# M594B.net
KiCad netlist of a schematic drawn in EAGLE
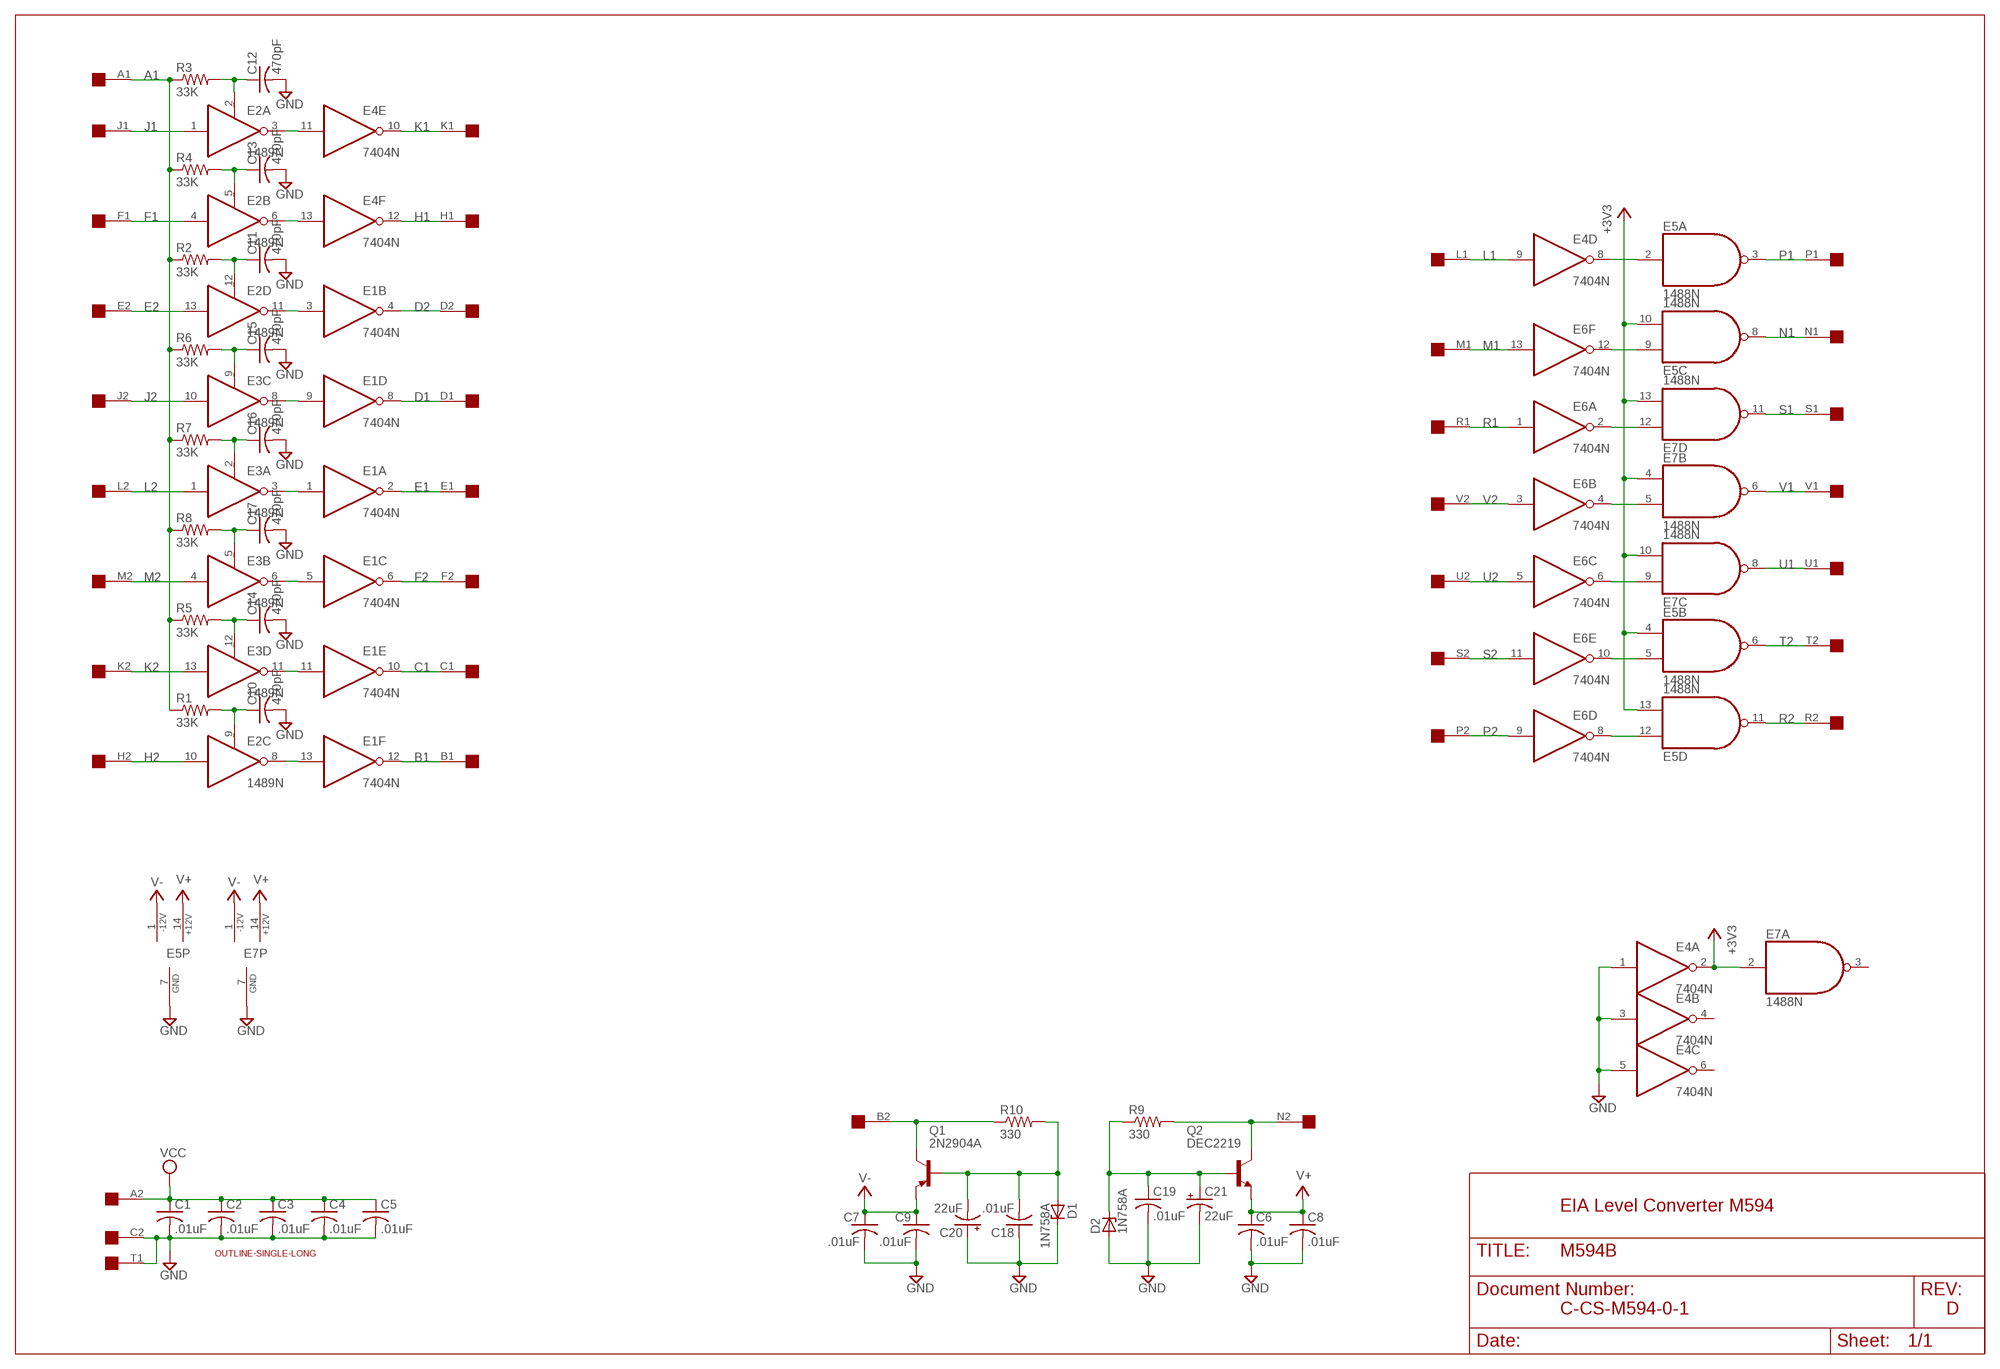
[diagram p0: schematic, sheet 1]

(export (version "E")
  (design (tool "Eeschema 10.0.6"))
  (components
    (comp (ref "C1")
      (value ".01uF")
      (footprint "eagle-import:C050-025X075")
      (libsource (lib "eagle-import") (part "C-US050-025X075"))
    )
    (comp (ref "C2")
      (value ".01uF")
      (footprint "eagle-import:C050-025X075")
      (libsource (lib "eagle-import") (part "C-US050-025X075"))
    )
    (comp (ref "C3")
      (value ".01uF")
      (footprint "eagle-import:C050-025X075")
      (libsource (lib "eagle-import") (part "C-US050-025X075"))
    )
    (comp (ref "C4")
      (value ".01uF")
      (footprint "eagle-import:C050-025X075")
      (libsource (lib "eagle-import") (part "C-US050-025X075"))
    )
    (comp (ref "C5")
      (value ".01uF")
      (footprint "eagle-import:C050-025X075")
      (libsource (lib "eagle-import") (part "C-US050-025X075"))
    )
    (comp (ref "C6")
      (value ".01uF")
      (footprint "eagle-import:C050-025X075")
      (libsource (lib "eagle-import") (part "C-US050-025X075"))
    )
    (comp (ref "C7")
      (value ".01uF")
      (footprint "eagle-import:C050-025X075")
      (libsource (lib "eagle-import") (part "C-US050-025X075"))
    )
    (comp (ref "C8")
      (value ".01uF")
      (footprint "eagle-import:C050-025X075")
      (libsource (lib "eagle-import") (part "C-US050-025X075"))
    )
    (comp (ref "C9")
      (value ".01uF")
      (footprint "eagle-import:C050-025X075")
      (libsource (lib "eagle-import") (part "C-US050-025X075"))
    )
    (comp (ref "C10")
      (value "470pF")
      (footprint "eagle-import:C075-032X103")
      (libsource (lib "eagle-import") (part "C-US075-032X103"))
    )
    (comp (ref "C11")
      (value "470pF")
      (footprint "eagle-import:C075-032X103")
      (libsource (lib "eagle-import") (part "C-US075-032X103"))
    )
    (comp (ref "C12")
      (value "470pF")
      (footprint "eagle-import:C075-032X103")
      (libsource (lib "eagle-import") (part "C-US075-032X103"))
    )
    (comp (ref "C13")
      (value "470pF")
      (footprint "eagle-import:C075-032X103")
      (libsource (lib "eagle-import") (part "C-US075-032X103"))
    )
    (comp (ref "C14")
      (value "470pF")
      (footprint "eagle-import:C075-032X103")
      (libsource (lib "eagle-import") (part "C-US075-032X103"))
    )
    (comp (ref "C15")
      (value "470pF")
      (footprint "eagle-import:C075-032X103")
      (libsource (lib "eagle-import") (part "C-US075-032X103"))
    )
    (comp (ref "C16")
      (value "470pF")
      (footprint "eagle-import:C075-032X103")
      (libsource (lib "eagle-import") (part "C-US075-032X103"))
    )
    (comp (ref "C17")
      (value "470pF")
      (footprint "eagle-import:C075-032X103")
      (libsource (lib "eagle-import") (part "C-US075-032X103"))
    )
    (comp (ref "C18")
      (value ".01uF")
      (footprint "eagle-import:C050-025X075")
      (libsource (lib "eagle-import") (part "C-US050-025X075"))
    )
    (comp (ref "C19")
      (value ".01uF")
      (footprint "eagle-import:C050-025X075")
      (libsource (lib "eagle-import") (part "C-US050-025X075"))
    )
    (comp (ref "C20")
      (value "22uF")
      (footprint "eagle-import:E12-8")
      (libsource (lib "eagle-import") (part "CPOL-USE20-8AXIAL"))
    )
    (comp (ref "C21")
      (value "22uF")
      (footprint "eagle-import:E12-8")
      (libsource (lib "eagle-import") (part "CPOL-USE20-8AXIAL"))
    )
    (comp (ref "D1")
      (value "1N758A")
      (footprint "eagle-import:DO35Z10")
      (libsource (lib "eagle-import") (part "ZENER-DIODEDO35Z10"))
    )
    (comp (ref "D2")
      (value "1N758A")
      (footprint "eagle-import:DO35Z10")
      (libsource (lib "eagle-import") (part "ZENER-DIODEDO35Z10"))
    )
    (comp (ref "E1")
      (value "7404N")
      (footprint "eagle-import:DIL14")
      (libsource (lib "eagle-import") (part "7404N"))
    )
    (comp (ref "E2")
      (value "1489N")
      (footprint "eagle-import:DIL14")
      (libsource (lib "eagle-import") (part "1489N"))
    )
    (comp (ref "E3")
      (value "1489N")
      (footprint "eagle-import:DIL14")
      (libsource (lib "eagle-import") (part "1489N"))
    )
    (comp (ref "E4")
      (value "7404N")
      (footprint "eagle-import:DIL14")
      (libsource (lib "eagle-import") (part "7404N"))
    )
    (comp (ref "E5")
      (value "1488N")
      (footprint "eagle-import:DIL14")
      (libsource (lib "eagle-import") (part "1488N"))
    )
    (comp (ref "E6")
      (value "7404N")
      (footprint "eagle-import:DIL14")
      (libsource (lib "eagle-import") (part "7404N"))
    )
    (comp (ref "E7")
      (value "1488N")
      (footprint "eagle-import:DIL14")
      (libsource (lib "eagle-import") (part "1488N"))
    )
    (comp (ref "Q1")
      (value "2N2904A")
      (footprint "eagle-import:TO5")
      (libsource (lib "eagle-import") (part "-PNP-TO5"))
    )
    (comp (ref "Q2")
      (value "DEC2219")
      (footprint "eagle-import:TO5")
      (libsource (lib "eagle-import") (part "-NPN-TO5"))
    )
    (comp (ref "R1")
      (value "33K")
      (footprint "eagle-import:0207_10")
      (libsource (lib "eagle-import") (part "R-US_0207/10"))
    )
    (comp (ref "R2")
      (value "33K")
      (footprint "eagle-import:0207_10")
      (libsource (lib "eagle-import") (part "R-US_0207/10"))
    )
    (comp (ref "R3")
      (value "33K")
      (footprint "eagle-import:0207_10")
      (libsource (lib "eagle-import") (part "R-US_0207/10"))
    )
    (comp (ref "R4")
      (value "33K")
      (footprint "eagle-import:0207_10")
      (libsource (lib "eagle-import") (part "R-US_0207/10"))
    )
    (comp (ref "R5")
      (value "33K")
      (footprint "eagle-import:0207_10")
      (libsource (lib "eagle-import") (part "R-US_0207/10"))
    )
    (comp (ref "R6")
      (value "33K")
      (footprint "eagle-import:0207_10")
      (libsource (lib "eagle-import") (part "R-US_0207/10"))
    )
    (comp (ref "R7")
      (value "33K")
      (footprint "eagle-import:0207_10")
      (libsource (lib "eagle-import") (part "R-US_0207/10"))
    )
    (comp (ref "R8")
      (value "33K")
      (footprint "eagle-import:0207_10")
      (libsource (lib "eagle-import") (part "R-US_0207/10"))
    )
    (comp (ref "R9")
      (value "330")
      (footprint "eagle-import:0207_10")
      (libsource (lib "eagle-import") (part "R-US_0207/10"))
    )
    (comp (ref "R10")
      (value "330")
      (footprint "eagle-import:0207_10")
      (libsource (lib "eagle-import") (part "R-US_0207/10"))
    )
    (comp (ref "U$1")
      (value "OUTLINE-SINGLE-LONG")
      (footprint "eagle-import:SINGLE-LONG")
      (libsource (lib "eagle-import") (part "OUTLINE-SINGLE-LONG"))
    )
    (comp (ref "U$2")
      (value "SINGLE")
      (footprint "eagle-import:EDGE-CON2")
      (libsource (lib "eagle-import") (part "SINGLE"))
    )
  )
  (nets
    (net (code "1") (name "+3V3") (class "Default")
      (node (ref "E4") (pin "2") (pinfunction "O_2") (pintype "output"))
      (node (ref "E5") (pin "10") (pinfunction "I1_10") (pintype "input"))
      (node (ref "E5") (pin "13") (pinfunction "I1_13") (pintype "input"))
      (node (ref "E5") (pin "4") (pinfunction "I0_4") (pintype "input"))
      (node (ref "E7") (pin "10") (pinfunction "I1_10") (pintype "input"))
      (node (ref "E7") (pin "13") (pinfunction "I1_13") (pintype "input"))
      (node (ref "E7") (pin "2") (pinfunction "I_2") (pintype "input"))
      (node (ref "E7") (pin "4") (pinfunction "I0_4") (pintype "input"))
    )
    (net (code "2") (name "/A1") (class "Default")
      (node (ref "R1") (pin "1") (pinfunction "1_1") (pintype "passive"))
      (node (ref "R2") (pin "1") (pinfunction "1_1") (pintype "passive"))
      (node (ref "R3") (pin "1") (pinfunction "1_1") (pintype "passive"))
      (node (ref "R4") (pin "1") (pinfunction "1_1") (pintype "passive"))
      (node (ref "R5") (pin "1") (pinfunction "1_1") (pintype "passive"))
      (node (ref "R6") (pin "1") (pinfunction "1_1") (pintype "passive"))
      (node (ref "R7") (pin "1") (pinfunction "1_1") (pintype "passive"))
      (node (ref "R8") (pin "1") (pinfunction "1_1") (pintype "passive"))
      (node (ref "U$2") (pin "A1") (pinfunction "1_A1") (pintype "bidirectional"))
    )
    (net (code "3") (name "/B1") (class "Default")
      (node (ref "E1") (pin "12") (pinfunction "O_12") (pintype "output"))
      (node (ref "U$2") (pin "B1") (pinfunction "1_B1") (pintype "bidirectional"))
    )
    (net (code "4") (name "/C1") (class "Default")
      (node (ref "E1") (pin "10") (pinfunction "O_10") (pintype "output"))
      (node (ref "U$2") (pin "C1") (pinfunction "1_C1") (pintype "bidirectional"))
    )
    (net (code "5") (name "/D1") (class "Default")
      (node (ref "E1") (pin "8") (pinfunction "O_8") (pintype "output"))
      (node (ref "U$2") (pin "D1") (pinfunction "1_D1") (pintype "bidirectional"))
    )
    (net (code "6") (name "/D2") (class "Default")
      (node (ref "E1") (pin "4") (pinfunction "O_4") (pintype "output"))
      (node (ref "U$2") (pin "D2") (pinfunction "1_D2") (pintype "bidirectional"))
    )
    (net (code "7") (name "/E1") (class "Default")
      (node (ref "E1") (pin "2") (pinfunction "O_2") (pintype "output"))
      (node (ref "U$2") (pin "E1") (pinfunction "1_E1") (pintype "bidirectional"))
    )
    (net (code "8") (name "/E2") (class "Default")
      (node (ref "E2") (pin "13") (pinfunction "I_13") (pintype "input"))
      (node (ref "U$2") (pin "E2") (pinfunction "1_E2") (pintype "bidirectional"))
    )
    (net (code "9") (name "/F1") (class "Default")
      (node (ref "E2") (pin "4") (pinfunction "I_4") (pintype "input"))
      (node (ref "U$2") (pin "F1") (pinfunction "1_F1") (pintype "bidirectional"))
    )
    (net (code "10") (name "/F2") (class "Default")
      (node (ref "E1") (pin "6") (pinfunction "O_6") (pintype "output"))
      (node (ref "U$2") (pin "F2") (pinfunction "1_F2") (pintype "bidirectional"))
    )
    (net (code "11") (name "/H1") (class "Default")
      (node (ref "E4") (pin "12") (pinfunction "O_12") (pintype "output"))
      (node (ref "U$2") (pin "H1") (pinfunction "1_H1") (pintype "bidirectional"))
    )
    (net (code "12") (name "/H2") (class "Default")
      (node (ref "E2") (pin "10") (pinfunction "I_10") (pintype "input"))
      (node (ref "U$2") (pin "H2") (pinfunction "1_H2") (pintype "bidirectional"))
    )
    (net (code "13") (name "/J1") (class "Default")
      (node (ref "E2") (pin "1") (pinfunction "I_1") (pintype "input"))
      (node (ref "U$2") (pin "J1") (pinfunction "1_J1") (pintype "bidirectional"))
    )
    (net (code "14") (name "/J2") (class "Default")
      (node (ref "E3") (pin "10") (pinfunction "I_10") (pintype "input"))
      (node (ref "U$2") (pin "J2") (pinfunction "1_J2") (pintype "bidirectional"))
    )
    (net (code "15") (name "/K1") (class "Default")
      (node (ref "E4") (pin "10") (pinfunction "O_10") (pintype "output"))
      (node (ref "U$2") (pin "K1") (pinfunction "1_K1") (pintype "bidirectional"))
    )
    (net (code "16") (name "/K2") (class "Default")
      (node (ref "E3") (pin "13") (pinfunction "I_13") (pintype "input"))
      (node (ref "U$2") (pin "K2") (pinfunction "1_K2") (pintype "bidirectional"))
    )
    (net (code "17") (name "/L1") (class "Default")
      (node (ref "E4") (pin "9") (pinfunction "I_9") (pintype "input"))
      (node (ref "U$2") (pin "L1") (pinfunction "1_L1") (pintype "bidirectional"))
    )
    (net (code "18") (name "/L2") (class "Default")
      (node (ref "E3") (pin "1") (pinfunction "I_1") (pintype "input"))
      (node (ref "U$2") (pin "L2") (pinfunction "1_L2") (pintype "bidirectional"))
    )
    (net (code "19") (name "/M1") (class "Default")
      (node (ref "E6") (pin "13") (pinfunction "I_13") (pintype "input"))
      (node (ref "U$2") (pin "M1") (pinfunction "1_M1") (pintype "bidirectional"))
    )
    (net (code "20") (name "/M2") (class "Default")
      (node (ref "E3") (pin "4") (pinfunction "I_4") (pintype "input"))
      (node (ref "U$2") (pin "M2") (pinfunction "1_M2") (pintype "bidirectional"))
    )
    (net (code "21") (name "/N1") (class "Default")
      (node (ref "E5") (pin "8") (pinfunction "O_8") (pintype "output"))
      (node (ref "U$2") (pin "N1") (pinfunction "1_N1") (pintype "bidirectional"))
    )
    (net (code "22") (name "/P1") (class "Default")
      (node (ref "E5") (pin "3") (pinfunction "O_3") (pintype "output"))
      (node (ref "U$2") (pin "P1") (pinfunction "1_P1") (pintype "bidirectional"))
    )
    (net (code "23") (name "/P2") (class "Default")
      (node (ref "E6") (pin "9") (pinfunction "I_9") (pintype "input"))
      (node (ref "U$2") (pin "P2") (pinfunction "1_P2") (pintype "bidirectional"))
    )
    (net (code "24") (name "/R1") (class "Default")
      (node (ref "E6") (pin "1") (pinfunction "I_1") (pintype "input"))
      (node (ref "U$2") (pin "R1") (pinfunction "1_R1") (pintype "bidirectional"))
    )
    (net (code "25") (name "/R2") (class "Default")
      (node (ref "E5") (pin "11") (pinfunction "O_11") (pintype "output"))
      (node (ref "U$2") (pin "R2") (pinfunction "1_R2") (pintype "bidirectional"))
    )
    (net (code "26") (name "/S1") (class "Default")
      (node (ref "E7") (pin "11") (pinfunction "O_11") (pintype "output"))
      (node (ref "U$2") (pin "S1") (pinfunction "1_S1") (pintype "bidirectional"))
    )
    (net (code "27") (name "/S2") (class "Default")
      (node (ref "E6") (pin "11") (pinfunction "I_11") (pintype "input"))
      (node (ref "U$2") (pin "S2") (pinfunction "1_S2") (pintype "bidirectional"))
    )
    (net (code "28") (name "/T2") (class "Default")
      (node (ref "E5") (pin "6") (pinfunction "O_6") (pintype "output"))
      (node (ref "U$2") (pin "T2") (pinfunction "1_T2") (pintype "bidirectional"))
    )
    (net (code "29") (name "/U1") (class "Default")
      (node (ref "E7") (pin "8") (pinfunction "O_8") (pintype "output"))
      (node (ref "U$2") (pin "U1") (pinfunction "1_U1") (pintype "bidirectional"))
    )
    (net (code "30") (name "/U2") (class "Default")
      (node (ref "E6") (pin "5") (pinfunction "I_5") (pintype "input"))
      (node (ref "U$2") (pin "U2") (pinfunction "1_U2") (pintype "bidirectional"))
    )
    (net (code "31") (name "/V1") (class "Default")
      (node (ref "E7") (pin "6") (pinfunction "O_6") (pintype "output"))
      (node (ref "U$2") (pin "V1") (pinfunction "1_V1") (pintype "bidirectional"))
    )
    (net (code "32") (name "/V2") (class "Default")
      (node (ref "E6") (pin "3") (pinfunction "I_3") (pintype "input"))
      (node (ref "U$2") (pin "V2") (pinfunction "1_V2") (pintype "bidirectional"))
    )
    (net (code "33") (name "GND") (class "Default")
      (node (ref "C1") (pin "2") (pinfunction "2_2") (pintype "passive"))
      (node (ref "C10") (pin "2") (pinfunction "2_2") (pintype "passive"))
      (node (ref "C11") (pin "2") (pinfunction "2_2") (pintype "passive"))
      (node (ref "C12") (pin "2") (pinfunction "2_2") (pintype "passive"))
      (node (ref "C13") (pin "2") (pinfunction "2_2") (pintype "passive"))
      (node (ref "C14") (pin "2") (pinfunction "2_2") (pintype "passive"))
      (node (ref "C15") (pin "2") (pinfunction "2_2") (pintype "passive"))
      (node (ref "C16") (pin "2") (pinfunction "2_2") (pintype "passive"))
      (node (ref "C17") (pin "2") (pinfunction "2_2") (pintype "passive"))
      (node (ref "C18") (pin "1") (pinfunction "1_1") (pintype "passive"))
      (node (ref "C19") (pin "2") (pinfunction "2_2") (pintype "passive"))
      (node (ref "C2") (pin "2") (pinfunction "2_2") (pintype "passive"))
      (node (ref "C20") (pin "+") (pinfunction "+_+") (pintype "passive"))
      (node (ref "C21") (pin "-") (pinfunction "-_-") (pintype "passive"))
      (node (ref "C3") (pin "2") (pinfunction "2_2") (pintype "passive"))
      (node (ref "C4") (pin "2") (pinfunction "2_2") (pintype "passive"))
      (node (ref "C5") (pin "2") (pinfunction "2_2") (pintype "passive"))
      (node (ref "C6") (pin "2") (pinfunction "2_2") (pintype "passive"))
      (node (ref "C7") (pin "2") (pinfunction "2_2") (pintype "passive"))
      (node (ref "C8") (pin "2") (pinfunction "2_2") (pintype "passive"))
      (node (ref "C9") (pin "2") (pinfunction "2_2") (pintype "passive"))
      (node (ref "D1") (pin "C") (pinfunction "C_C") (pintype "passive"))
      (node (ref "D2") (pin "A") (pinfunction "A_A") (pintype "passive"))
      (node (ref "E4") (pin "1") (pinfunction "I_1") (pintype "input"))
      (node (ref "E4") (pin "3") (pinfunction "I_3") (pintype "input"))
      (node (ref "E4") (pin "5") (pinfunction "I_5") (pintype "input"))
      (node (ref "E5") (pin "7") (pinfunction "GND_7") (pintype "power_in"))
      (node (ref "E7") (pin "7") (pinfunction "GND_7") (pintype "power_in"))
      (node (ref "U$2") (pin "C2") (pinfunction "1_C2") (pintype "bidirectional"))
      (node (ref "U$2") (pin "T1") (pinfunction "1_T1") (pintype "bidirectional"))
    )
    (net (code "34") (name "Net-(E1A-I)") (class "Default")
      (node (ref "E1") (pin "1") (pinfunction "I_1") (pintype "input"))
      (node (ref "E3") (pin "3") (pinfunction "O_3") (pintype "output"))
    )
    (net (code "35") (name "Net-(E1B-I)") (class "Default")
      (node (ref "E1") (pin "3") (pinfunction "I_3") (pintype "input"))
      (node (ref "E2") (pin "11") (pinfunction "O_11") (pintype "output"))
    )
    (net (code "36") (name "Net-(E1C-I)") (class "Default")
      (node (ref "E1") (pin "5") (pinfunction "I_5") (pintype "input"))
      (node (ref "E3") (pin "6") (pinfunction "O_6") (pintype "output"))
    )
    (net (code "37") (name "Net-(E1D-I)") (class "Default")
      (node (ref "E1") (pin "9") (pinfunction "I_9") (pintype "input"))
      (node (ref "E3") (pin "8") (pinfunction "O_8") (pintype "output"))
    )
    (net (code "38") (name "Net-(E1E-I)") (class "Default")
      (node (ref "E1") (pin "11") (pinfunction "I_11") (pintype "input"))
      (node (ref "E3") (pin "11") (pinfunction "O_11") (pintype "output"))
    )
    (net (code "39") (name "Net-(E1F-I)") (class "Default")
      (node (ref "E1") (pin "13") (pinfunction "I_13") (pintype "input"))
      (node (ref "E2") (pin "8") (pinfunction "O_8") (pintype "output"))
    )
    (net (code "40") (name "Net-(E2A-O)") (class "Default")
      (node (ref "E2") (pin "3") (pinfunction "O_3") (pintype "output"))
      (node (ref "E4") (pin "11") (pinfunction "I_11") (pintype "input"))
    )
    (net (code "41") (name "Net-(E2A-RC)") (class "Default")
      (node (ref "C12") (pin "1") (pinfunction "1_1") (pintype "passive"))
      (node (ref "E2") (pin "2") (pinfunction "RC_2") (pintype "input"))
      (node (ref "R3") (pin "2") (pinfunction "2_2") (pintype "passive"))
    )
    (net (code "42") (name "Net-(E2B-O)") (class "Default")
      (node (ref "E2") (pin "6") (pinfunction "O_6") (pintype "output"))
      (node (ref "E4") (pin "13") (pinfunction "I_13") (pintype "input"))
    )
    (net (code "43") (name "Net-(E2B-RC)") (class "Default")
      (node (ref "C13") (pin "1") (pinfunction "1_1") (pintype "passive"))
      (node (ref "E2") (pin "5") (pinfunction "RC_5") (pintype "input"))
      (node (ref "R4") (pin "2") (pinfunction "2_2") (pintype "passive"))
    )
    (net (code "44") (name "Net-(E2C-RC)") (class "Default")
      (node (ref "C10") (pin "1") (pinfunction "1_1") (pintype "passive"))
      (node (ref "E2") (pin "9") (pinfunction "RC_9") (pintype "input"))
      (node (ref "R1") (pin "2") (pinfunction "2_2") (pintype "passive"))
    )
    (net (code "45") (name "Net-(E2D-RC)") (class "Default")
      (node (ref "C11") (pin "1") (pinfunction "1_1") (pintype "passive"))
      (node (ref "E2") (pin "12") (pinfunction "RC_12") (pintype "input"))
      (node (ref "R2") (pin "2") (pinfunction "2_2") (pintype "passive"))
    )
    (net (code "46") (name "Net-(E3A-RC)") (class "Default")
      (node (ref "C16") (pin "1") (pinfunction "1_1") (pintype "passive"))
      (node (ref "E3") (pin "2") (pinfunction "RC_2") (pintype "input"))
      (node (ref "R7") (pin "2") (pinfunction "2_2") (pintype "passive"))
    )
    (net (code "47") (name "Net-(E3B-RC)") (class "Default")
      (node (ref "C17") (pin "1") (pinfunction "1_1") (pintype "passive"))
      (node (ref "E3") (pin "5") (pinfunction "RC_5") (pintype "input"))
      (node (ref "R8") (pin "2") (pinfunction "2_2") (pintype "passive"))
    )
    (net (code "48") (name "Net-(E3C-RC)") (class "Default")
      (node (ref "C15") (pin "1") (pinfunction "1_1") (pintype "passive"))
      (node (ref "E3") (pin "9") (pinfunction "RC_9") (pintype "input"))
      (node (ref "R6") (pin "2") (pinfunction "2_2") (pintype "passive"))
    )
    (net (code "49") (name "Net-(E3D-RC)") (class "Default")
      (node (ref "C14") (pin "1") (pinfunction "1_1") (pintype "passive"))
      (node (ref "E3") (pin "12") (pinfunction "RC_12") (pintype "input"))
      (node (ref "R5") (pin "2") (pinfunction "2_2") (pintype "passive"))
    )
    (net (code "50") (name "Net-(E4D-O)") (class "Default")
      (node (ref "E4") (pin "8") (pinfunction "O_8") (pintype "output"))
      (node (ref "E5") (pin "2") (pinfunction "I_2") (pintype "input"))
    )
    (net (code "51") (name "Net-(E5B-I1)") (class "Default")
      (node (ref "E5") (pin "5") (pinfunction "I1_5") (pintype "input"))
      (node (ref "E6") (pin "10") (pinfunction "O_10") (pintype "output"))
    )
    (net (code "52") (name "Net-(E5C-I0)") (class "Default")
      (node (ref "E5") (pin "9") (pinfunction "I0_9") (pintype "input"))
      (node (ref "E6") (pin "12") (pinfunction "O_12") (pintype "output"))
    )
    (net (code "53") (name "Net-(E5D-I0)") (class "Default")
      (node (ref "E5") (pin "12") (pinfunction "I0_12") (pintype "input"))
      (node (ref "E6") (pin "8") (pinfunction "O_8") (pintype "output"))
    )
    (net (code "54") (name "Net-(E6A-O)") (class "Default")
      (node (ref "E6") (pin "2") (pinfunction "O_2") (pintype "output"))
      (node (ref "E7") (pin "12") (pinfunction "I0_12") (pintype "input"))
    )
    (net (code "55") (name "Net-(E6B-O)") (class "Default")
      (node (ref "E6") (pin "4") (pinfunction "O_4") (pintype "output"))
      (node (ref "E7") (pin "5") (pinfunction "I1_5") (pintype "input"))
    )
    (net (code "56") (name "Net-(E6C-O)") (class "Default")
      (node (ref "E6") (pin "6") (pinfunction "O_6") (pintype "output"))
      (node (ref "E7") (pin "9") (pinfunction "I0_9") (pintype "input"))
    )
    (net (code "57") (name "Net-(Q1-B)") (class "Default")
      (node (ref "C18") (pin "2") (pinfunction "2_2") (pintype "passive"))
      (node (ref "C20") (pin "-") (pinfunction "-_-") (pintype "passive"))
      (node (ref "D1") (pin "A") (pinfunction "A_A") (pintype "passive"))
      (node (ref "Q1") (pin "2") (pinfunction "B_2") (pintype "passive"))
      (node (ref "R10") (pin "2") (pinfunction "2_2") (pintype "passive"))
    )
    (net (code "58") (name "Net-(Q1-C)") (class "Default")
      (node (ref "Q1") (pin "3") (pinfunction "C_3") (pintype "passive"))
      (node (ref "R10") (pin "1") (pinfunction "1_1") (pintype "passive"))
      (node (ref "U$2") (pin "B2") (pinfunction "1_B2") (pintype "bidirectional"))
    )
    (net (code "59") (name "Net-(Q2-B)") (class "Default")
      (node (ref "C19") (pin "1") (pinfunction "1_1") (pintype "passive"))
      (node (ref "C21") (pin "+") (pinfunction "+_+") (pintype "passive"))
      (node (ref "D2") (pin "C") (pinfunction "C_C") (pintype "passive"))
      (node (ref "Q2") (pin "2") (pinfunction "B_2") (pintype "passive"))
      (node (ref "R9") (pin "1") (pinfunction "1_1") (pintype "passive"))
    )
    (net (code "60") (name "Net-(Q2-C)") (class "Default")
      (node (ref "Q2") (pin "3") (pinfunction "C_3") (pintype "passive"))
      (node (ref "R9") (pin "2") (pinfunction "2_2") (pintype "passive"))
      (node (ref "U$2") (pin "N2") (pinfunction "1_N2") (pintype "bidirectional"))
    )
    (net (code "61") (name "V+") (class "Default")
      (node (ref "C6") (pin "1") (pinfunction "1_1") (pintype "passive"))
      (node (ref "C8") (pin "1") (pinfunction "1_1") (pintype "passive"))
      (node (ref "E5") (pin "14") (pinfunction "+12V_14") (pintype "power_in"))
      (node (ref "E7") (pin "14") (pinfunction "+12V_14") (pintype "power_in"))
      (node (ref "Q2") (pin "1") (pinfunction "E_1") (pintype "passive"))
    )
    (net (code "62") (name "V-") (class "Default")
      (node (ref "C7") (pin "1") (pinfunction "1_1") (pintype "passive"))
      (node (ref "C9") (pin "1") (pinfunction "1_1") (pintype "passive"))
      (node (ref "E5") (pin "1") (pinfunction "-12V_1") (pintype "power_in"))
      (node (ref "E7") (pin "1") (pinfunction "-12V_1") (pintype "power_in"))
      (node (ref "Q1") (pin "1") (pinfunction "E_1") (pintype "passive"))
    )
    (net (code "63") (name "VCC") (class "Default")
      (node (ref "C1") (pin "1") (pinfunction "1_1") (pintype "passive"))
      (node (ref "C2") (pin "1") (pinfunction "1_1") (pintype "passive"))
      (node (ref "C3") (pin "1") (pinfunction "1_1") (pintype "passive"))
      (node (ref "C4") (pin "1") (pinfunction "1_1") (pintype "passive"))
      (node (ref "C5") (pin "1") (pinfunction "1_1") (pintype "passive"))
      (node (ref "U$2") (pin "A2") (pinfunction "1_A2") (pintype "bidirectional"))
    )
    (net (code "64") (name "unconnected-(E4B-O-Pad4)") (class "Default")
      (node (ref "E4") (pin "4") (pinfunction "O_4") (pintype "output"))
    )
    (net (code "65") (name "unconnected-(E4C-O-Pad6)") (class "Default")
      (node (ref "E4") (pin "6") (pinfunction "O_6") (pintype "output"))
    )
    (net (code "66") (name "unconnected-(E7A-O-Pad3)") (class "Default")
      (node (ref "E7") (pin "3") (pinfunction "O_3") (pintype "output"))
    )
  )
)
